# CMoy_-_OPA1622_Triple.net
KiCad netlist of a schematic drawn in EAGLE
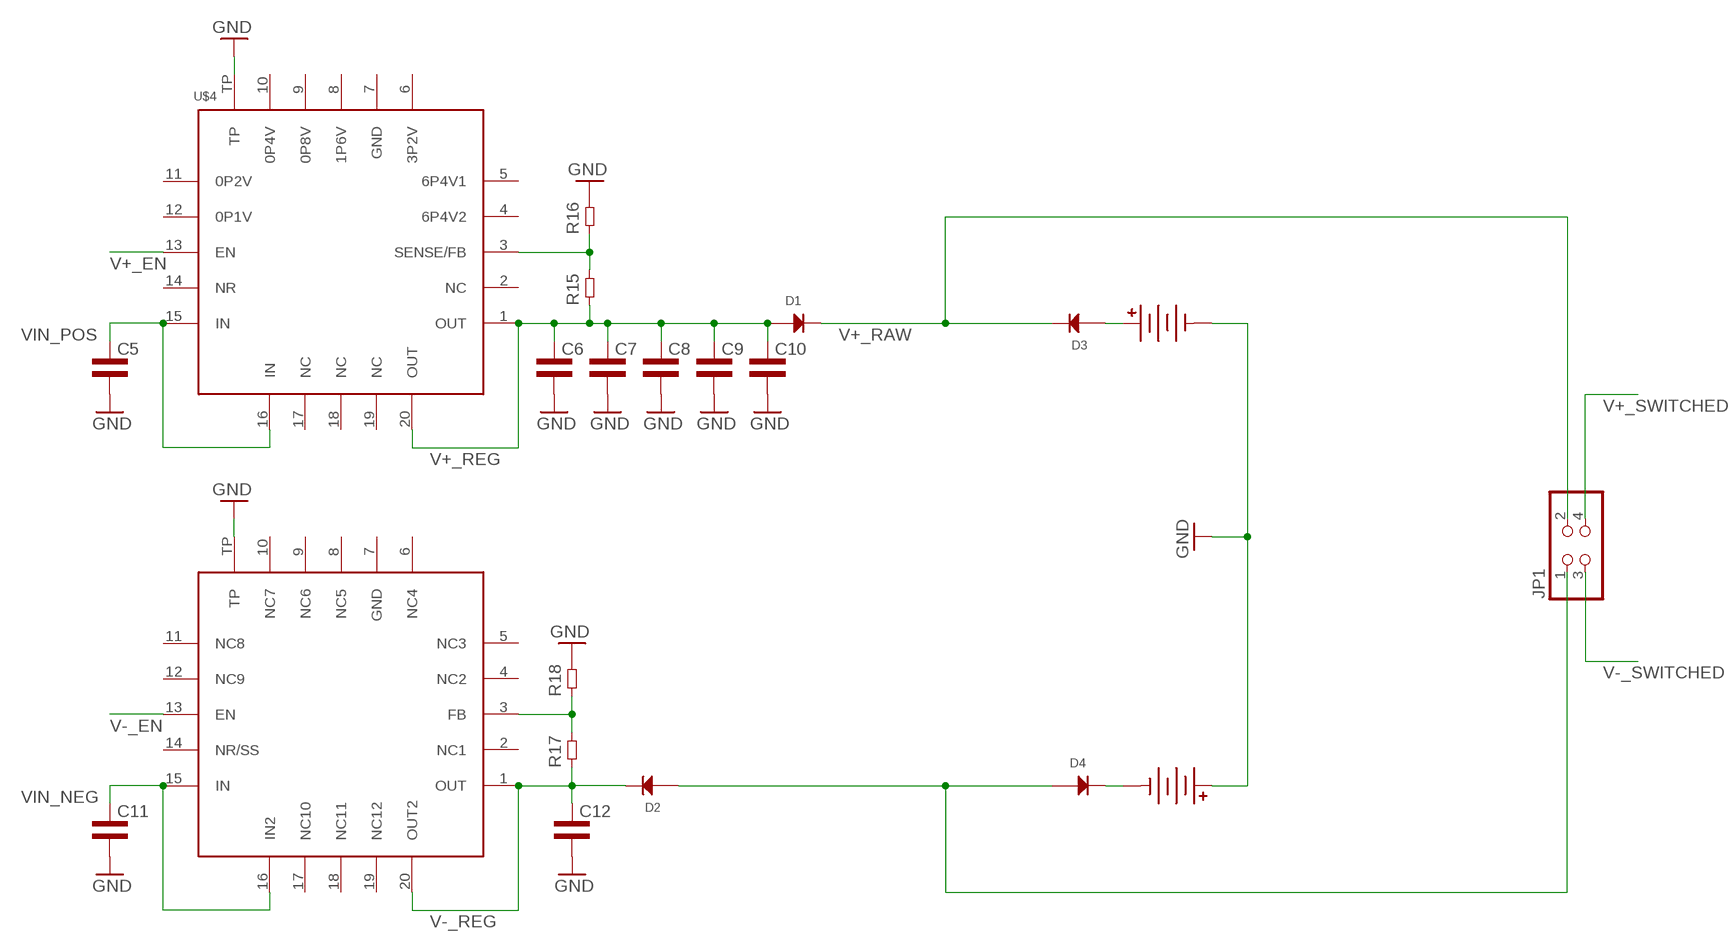
[diagram p0: schematic, sheet 1]
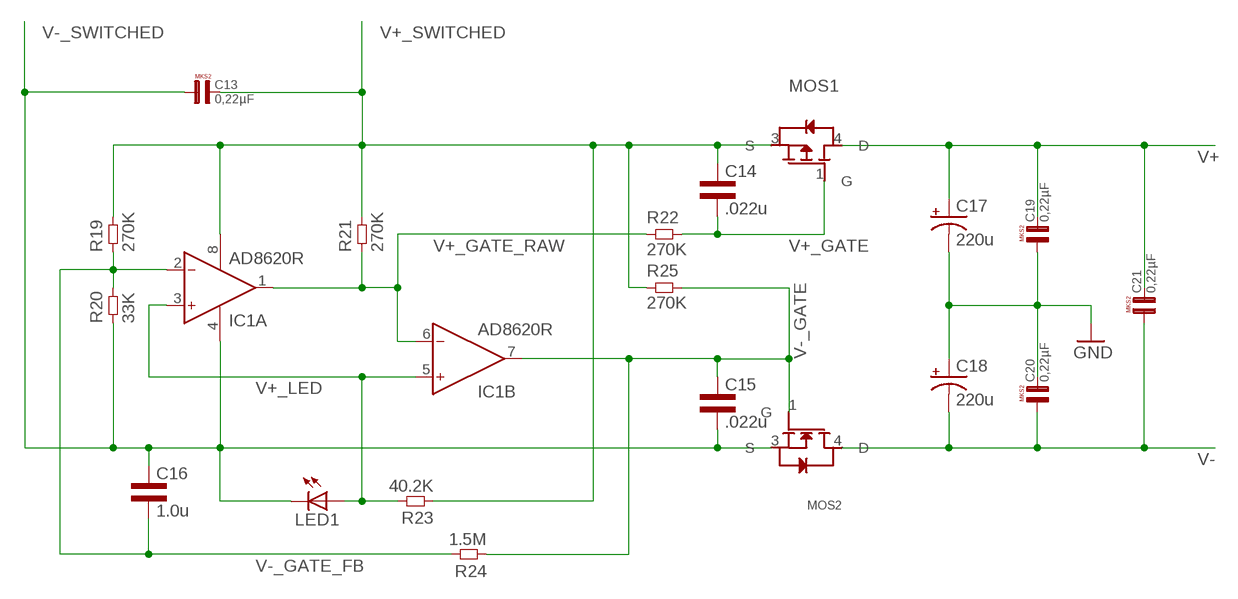
[diagram p1: schematic, sheet 2]
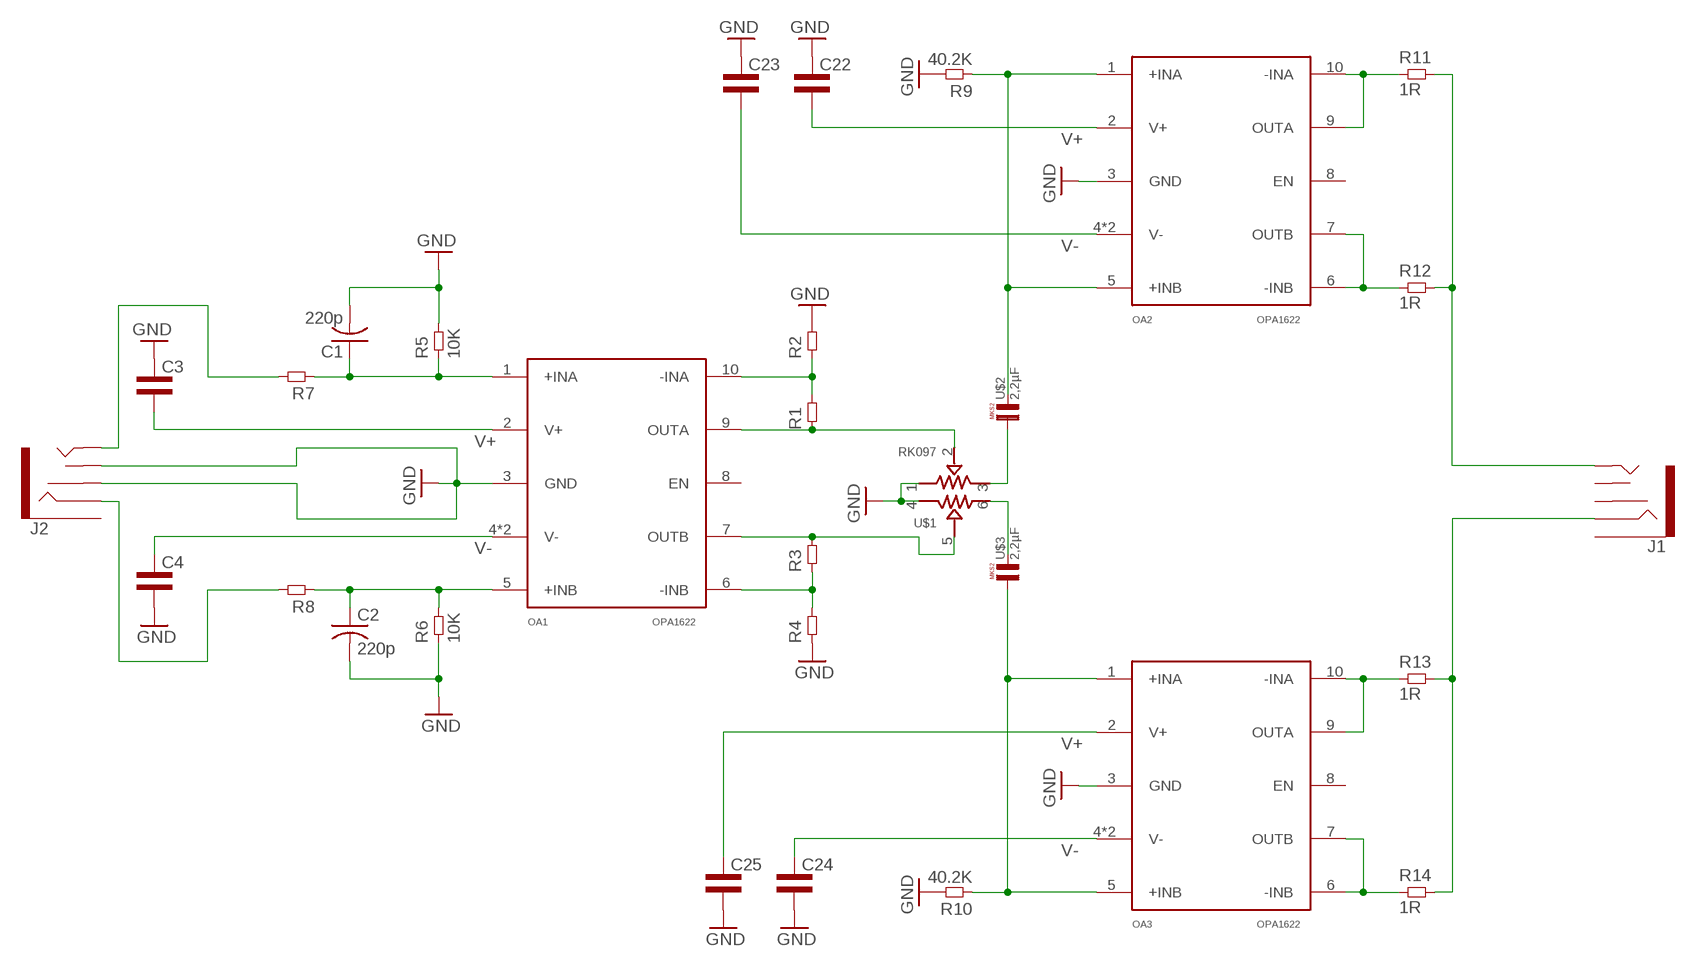
[diagram p2: schematic, sheet 3]

(export (version "E")
  (design (tool "Eeschema 10.0.6"))
  (components
    (comp (ref "C1")
      (value "220p")
      (footprint "eagle-import:C025-050X050")
      (libsource (lib "eagle-import") (part "C-US025-050X050"))
    )
    (comp (ref "C2")
      (value "220p")
      (footprint "eagle-import:C025-050X050")
      (libsource (lib "eagle-import") (part "C-US025-050X050"))
    )
    (comp (ref "C3")
      (value "CAP0603L3")
      (footprint "eagle-import:0603L3")
      (libsource (lib "eagle-import") (part "CAP0603L3"))
    )
    (comp (ref "C4")
      (value "CAP0603L3")
      (footprint "eagle-import:0603L3")
      (libsource (lib "eagle-import") (part "CAP0603L3"))
    )
    (comp (ref "C22")
      (value "CAP0603L3")
      (footprint "eagle-import:0603L3")
      (libsource (lib "eagle-import") (part "CAP0603L3"))
    )
    (comp (ref "C23")
      (value "CAP0603L3")
      (footprint "eagle-import:0603L3")
      (libsource (lib "eagle-import") (part "CAP0603L3"))
    )
    (comp (ref "C24")
      (value "CAP0603L3")
      (footprint "eagle-import:0603L3")
      (libsource (lib "eagle-import") (part "CAP0603L3"))
    )
    (comp (ref "C25")
      (value "CAP0603L3")
      (footprint "eagle-import:0603L3")
      (libsource (lib "eagle-import") (part "CAP0603L3"))
    )
    (comp (ref "J1")
      (value "AUDIO-JACK2SMD")
      (footprint "eagle-import:AUDIO-JACK-3.5MM-SMD")
      (libsource (lib "eagle-import") (part "AUDIO-JACK2SMD"))
    )
    (comp (ref "J2")
      (value "AUDIO-JACK2SMD")
      (footprint "eagle-import:AUDIO-JACK-3.5MM-SMD")
      (libsource (lib "eagle-import") (part "AUDIO-JACK2SMD"))
    )
    (comp (ref "OA1")
      (value "OPA1622")
      (footprint "eagle-import:S-PVSON-N10")
      (libsource (lib "eagle-import") (part "OPA1622"))
    )
    (comp (ref "OA2")
      (value "OPA1622")
      (footprint "eagle-import:S-PVSON-N10")
      (libsource (lib "eagle-import") (part "OPA1622"))
    )
    (comp (ref "OA3")
      (value "OPA1622")
      (footprint "eagle-import:S-PVSON-N10")
      (libsource (lib "eagle-import") (part "OPA1622"))
    )
    (comp (ref "R1")
      (value "RES0603L3")
      (footprint "eagle-import:0603L3")
      (libsource (lib "eagle-import") (part "RES0603L3"))
    )
    (comp (ref "R2")
      (value "RES0603L3")
      (footprint "eagle-import:0603L3")
      (libsource (lib "eagle-import") (part "RES0603L3"))
    )
    (comp (ref "R3")
      (value "RES0603L3")
      (footprint "eagle-import:0603L3")
      (libsource (lib "eagle-import") (part "RES0603L3"))
    )
    (comp (ref "R4")
      (value "RES0603L3")
      (footprint "eagle-import:0603L3")
      (libsource (lib "eagle-import") (part "RES0603L3"))
    )
    (comp (ref "R5")
      (value "10K")
      (footprint "eagle-import:0603L3")
      (libsource (lib "eagle-import") (part "RES0603L3"))
    )
    (comp (ref "R6")
      (value "10K")
      (footprint "eagle-import:0603L3")
      (libsource (lib "eagle-import") (part "RES0603L3"))
    )
    (comp (ref "R7")
      (value "RES0603L3")
      (footprint "eagle-import:0603L3")
      (libsource (lib "eagle-import") (part "RES0603L3"))
    )
    (comp (ref "R8")
      (value "RES0603L3")
      (footprint "eagle-import:0603L3")
      (libsource (lib "eagle-import") (part "RES0603L3"))
    )
    (comp (ref "R9")
      (value "40.2K")
      (footprint "eagle-import:0603L3")
      (libsource (lib "eagle-import") (part "RES0603L3"))
    )
    (comp (ref "R10")
      (value "40.2K")
      (footprint "eagle-import:0603L3")
      (libsource (lib "eagle-import") (part "RES0603L3"))
    )
    (comp (ref "R11")
      (value "1R")
      (footprint "eagle-import:0805L3")
      (libsource (lib "eagle-import") (part "RES0805L3"))
    )
    (comp (ref "R12")
      (value "1R")
      (footprint "eagle-import:0805L3")
      (libsource (lib "eagle-import") (part "RES0805L3"))
    )
    (comp (ref "R13")
      (value "1R")
      (footprint "eagle-import:0805L3")
      (libsource (lib "eagle-import") (part "RES0805L3"))
    )
    (comp (ref "R14")
      (value "1R")
      (footprint "eagle-import:0805L3")
      (libsource (lib "eagle-import") (part "RES0805L3"))
    )
    (comp (ref "U$1")
      (value "RK097")
      (footprint "eagle-import:RK097")
      (libsource (lib "eagle-import") (part "RK097"))
    )
    (comp (ref "U$2")
      (value "2,2µF")
      (footprint "eagle-import:R5B7K2")
      (libsource (lib "eagle-import") (part "2,2µF"))
    )
    (comp (ref "U$3")
      (value "2,2µF")
      (footprint "eagle-import:R5B7K2")
      (libsource (lib "eagle-import") (part "2,2µF"))
    )
    (comp (ref "BATT1")
      (value "BATT_9V")
      (footprint "eagle-import:9V_FEMALE")
      (libsource (lib "eagle-import") (part "BATT_9V"))
    )
    (comp (ref "BATT2")
      (value "BATT_9V")
      (footprint "eagle-import:9V_FEMALE")
      (libsource (lib "eagle-import") (part "BATT_9V"))
    )
    (comp (ref "C5")
      (value "CAP0805L3")
      (footprint "eagle-import:0805L3")
      (libsource (lib "eagle-import") (part "CAP0805L3"))
    )
    (comp (ref "C6")
      (value "CAP0805L3")
      (footprint "eagle-import:0805L3")
      (libsource (lib "eagle-import") (part "CAP0805L3"))
    )
    (comp (ref "C7")
      (value "CAP0805L3")
      (footprint "eagle-import:0805L3")
      (libsource (lib "eagle-import") (part "CAP0805L3"))
    )
    (comp (ref "C8")
      (value "CAP0805L3")
      (footprint "eagle-import:0805L3")
      (libsource (lib "eagle-import") (part "CAP0805L3"))
    )
    (comp (ref "C9")
      (value "CAP0805L3")
      (footprint "eagle-import:0805L3")
      (libsource (lib "eagle-import") (part "CAP0805L3"))
    )
    (comp (ref "C10")
      (value "CAP0805L3")
      (footprint "eagle-import:0805L3")
      (libsource (lib "eagle-import") (part "CAP0805L3"))
    )
    (comp (ref "C11")
      (value "CAP0805L3")
      (footprint "eagle-import:0805L3")
      (libsource (lib "eagle-import") (part "CAP0805L3"))
    )
    (comp (ref "C12")
      (value "CAP0805L3")
      (footprint "eagle-import:0805L3")
      (libsource (lib "eagle-import") (part "CAP0805L3"))
    )
    (comp (ref "D1")
      (value "DIODEMINI2-F3-B")
      (footprint "eagle-import:MINI2-F3-B")
      (libsource (lib "eagle-import") (part "DIODEMINI2-F3-B"))
    )
    (comp (ref "D2")
      (value "DIODEMINI2-F3-B")
      (footprint "eagle-import:MINI2-F3-B")
      (libsource (lib "eagle-import") (part "DIODEMINI2-F3-B"))
    )
    (comp (ref "D3")
      (value "DIODEMINI2-F3-B")
      (footprint "eagle-import:MINI2-F3-B")
      (libsource (lib "eagle-import") (part "DIODEMINI2-F3-B"))
    )
    (comp (ref "D4")
      (value "DIODEMINI2-F3-B")
      (footprint "eagle-import:MINI2-F3-B")
      (libsource (lib "eagle-import") (part "DIODEMINI2-F3-B"))
    )
    (comp (ref "JP1")
      (value "PINHD-2X2")
      (footprint "eagle-import:2X02")
      (libsource (lib "eagle-import") (part "PINHD-2X2"))
    )
    (comp (ref "R15")
      (value "RES0603L3")
      (footprint "eagle-import:0603L3")
      (libsource (lib "eagle-import") (part "RES0603L3"))
    )
    (comp (ref "R16")
      (value "RES0603L3")
      (footprint "eagle-import:0603L3")
      (libsource (lib "eagle-import") (part "RES0603L3"))
    )
    (comp (ref "R17")
      (value "RES0603L3")
      (footprint "eagle-import:0603L3")
      (libsource (lib "eagle-import") (part "RES0603L3"))
    )
    (comp (ref "R18")
      (value "RES0603L3")
      (footprint "eagle-import:0603L3")
      (libsource (lib "eagle-import") (part "RES0603L3"))
    )
    (comp (ref "U$4")
      (value "POWER-SUPPLY_POS_V1_TI_LDO_TPS7A4700")
      (footprint "eagle-import:POWER-SUPPLY_POS_V1_TI_LDO_VQFN-20")
      (libsource (lib "eagle-import") (part "POWER-SUPPLY_POS_V1_TI_LDO_TPS7A4700"))
    )
    (comp (ref "U$5")
      (value "POWER-SUPPLY_POS_V1_TI_LDO_TPS7A3301RGWT")
      (footprint "eagle-import:POWER-SUPPLY_POS_V1_TI_LDO_VQFN-20")
      (libsource (lib "eagle-import") (part "POWER-SUPPLY_POS_V1_TI_LDO_TPS7A3301RGWT"))
    )
    (comp (ref "C13")
      (value "0,22µF")
      (footprint "eagle-import:R5B3")
      (libsource (lib "eagle-import") (part "0,22µF"))
    )
    (comp (ref "C14")
      (value ".022u")
      (footprint "eagle-import:0603L3")
      (libsource (lib "eagle-import") (part "CAP0603L3"))
    )
    (comp (ref "C15")
      (value ".022u")
      (footprint "eagle-import:0603L3")
      (libsource (lib "eagle-import") (part "CAP0603L3"))
    )
    (comp (ref "C16")
      (value "1.0u")
      (footprint "eagle-import:0603L3")
      (libsource (lib "eagle-import") (part "CAP0603L3"))
    )
    (comp (ref "C17")
      (value "220u")
      (footprint "eagle-import:E3,5-8")
      (libsource (lib "eagle-import") (part "CPOL-USE3.5-8"))
    )
    (comp (ref "C18")
      (value "220u")
      (footprint "eagle-import:E3,5-8")
      (libsource (lib "eagle-import") (part "CPOL-USE3.5-8"))
    )
    (comp (ref "C19")
      (value "0,22µF")
      (footprint "eagle-import:R5B3")
      (libsource (lib "eagle-import") (part "0,22µF"))
    )
    (comp (ref "C20")
      (value "0,22µF")
      (footprint "eagle-import:R5B3")
      (libsource (lib "eagle-import") (part "0,22µF"))
    )
    (comp (ref "C21")
      (value "0,22µF")
      (footprint "eagle-import:R5B3")
      (libsource (lib "eagle-import") (part "0,22µF"))
    )
    (comp (ref "IC1")
      (value "AD8620R")
      (footprint "eagle-import:SO8")
      (fields (field (name "MF") "ALTERA CORPORATION") (field (name "MPN") "AD8620ARZ"))
      (libsource (lib "eagle-import") (part "AD8620R"))
    )
    (comp (ref "LED1")
      (value "LED3MM")
      (footprint "eagle-import:LED3MM")
      (libsource (lib "eagle-import") (part "LED3MM"))
    )
    (comp (ref "MOS1")
      (value "MOSFET-P")
      (footprint "eagle-import:DPAK-3")
      (libsource (lib "eagle-import") (part "MOSFET-P"))
    )
    (comp (ref "MOS2")
      (value "MOSFET-N")
      (footprint "eagle-import:DPAK-3")
      (libsource (lib "eagle-import") (part "MOSFET-N"))
    )
    (comp (ref "R19")
      (value "270K")
      (footprint "eagle-import:0603L3")
      (libsource (lib "eagle-import") (part "RES0603L3"))
    )
    (comp (ref "R20")
      (value "33K")
      (footprint "eagle-import:0603L3")
      (libsource (lib "eagle-import") (part "RES0603L3"))
    )
    (comp (ref "R21")
      (value "270K")
      (footprint "eagle-import:0603L3")
      (libsource (lib "eagle-import") (part "RES0603L3"))
    )
    (comp (ref "R22")
      (value "270K")
      (footprint "eagle-import:0603L3")
      (libsource (lib "eagle-import") (part "RES0603L3"))
    )
    (comp (ref "R23")
      (value "40.2K")
      (footprint "eagle-import:0603L3")
      (libsource (lib "eagle-import") (part "RES0603L3"))
    )
    (comp (ref "R24")
      (value "1.5M")
      (footprint "eagle-import:0603L3")
      (libsource (lib "eagle-import") (part "RES0603L3"))
    )
    (comp (ref "R25")
      (value "270K")
      (footprint "eagle-import:0603L3")
      (libsource (lib "eagle-import") (part "RES0603L3"))
    )
  )
  (nets
    (net (code "1") (name "GND") (class "Default")
      (node (ref "BATT1") (pin "N1") (pinfunction "NEG_N1") (pintype "bidirectional"))
      (node (ref "BATT1") (pin "N2") (pinfunction "NEG_N2") (pintype "bidirectional"))
      (node (ref "BATT1") (pin "N3") (pinfunction "NEG_N3") (pintype "bidirectional"))
      (node (ref "BATT2") (pin "P1") (pinfunction "POS_P1") (pintype "bidirectional"))
      (node (ref "BATT2") (pin "P2") (pinfunction "POS_P2") (pintype "bidirectional"))
      (node (ref "BATT2") (pin "P3") (pinfunction "POS_P3") (pintype "bidirectional"))
      (node (ref "C1") (pin "2") (pinfunction "2_2") (pintype "passive"))
      (node (ref "C10") (pin "2") (pinfunction "2_2") (pintype "bidirectional"))
      (node (ref "C11") (pin "2") (pinfunction "2_2") (pintype "bidirectional"))
      (node (ref "C12") (pin "2") (pinfunction "2_2") (pintype "bidirectional"))
      (node (ref "C17") (pin "-") (pinfunction "-_-") (pintype "passive"))
      (node (ref "C18") (pin "+") (pinfunction "+_+") (pintype "passive"))
      (node (ref "C19") (pin "1") (pinfunction "1_1") (pintype "passive"))
      (node (ref "C2") (pin "2") (pinfunction "2_2") (pintype "passive"))
      (node (ref "C20") (pin "2") (pinfunction "2_2") (pintype "passive"))
      (node (ref "C22") (pin "P$1") (pinfunction "1_P$1") (pintype "bidirectional"))
      (node (ref "C23") (pin "P$1") (pinfunction "1_P$1") (pintype "bidirectional"))
      (node (ref "C24") (pin "P$2") (pinfunction "2_P$2") (pintype "bidirectional"))
      (node (ref "C25") (pin "P$2") (pinfunction "2_P$2") (pintype "bidirectional"))
      (node (ref "C3") (pin "P$1") (pinfunction "1_P$1") (pintype "bidirectional"))
      (node (ref "C4") (pin "P$2") (pinfunction "2_P$2") (pintype "bidirectional"))
      (node (ref "C5") (pin "2") (pinfunction "2_2") (pintype "bidirectional"))
      (node (ref "C6") (pin "2") (pinfunction "2_2") (pintype "bidirectional"))
      (node (ref "C7") (pin "2") (pinfunction "2_2") (pintype "bidirectional"))
      (node (ref "C8") (pin "2") (pinfunction "2_2") (pintype "bidirectional"))
      (node (ref "C9") (pin "2") (pinfunction "2_2") (pintype "bidirectional"))
      (node (ref "J2") (pin "RSH") (pinfunction "RSH_RSH") (pintype "bidirectional"))
      (node (ref "J2") (pin "TSH") (pinfunction "TSH_TSH") (pintype "bidirectional"))
      (node (ref "OA1") (pin "3") (pinfunction "GND_3") (pintype "bidirectional"))
      (node (ref "OA2") (pin "3") (pinfunction "GND_3") (pintype "bidirectional"))
      (node (ref "OA3") (pin "3") (pinfunction "GND_3") (pintype "bidirectional"))
      (node (ref "R10") (pin "P$2") (pinfunction "2_P$2") (pintype "bidirectional"))
      (node (ref "R16") (pin "P$2") (pinfunction "2_P$2") (pintype "bidirectional"))
      (node (ref "R18") (pin "P$2") (pinfunction "2_P$2") (pintype "bidirectional"))
      (node (ref "R2") (pin "P$2") (pinfunction "2_P$2") (pintype "bidirectional"))
      (node (ref "R4") (pin "P$1") (pinfunction "1_P$1") (pintype "bidirectional"))
      (node (ref "R5") (pin "P$2") (pinfunction "2_P$2") (pintype "bidirectional"))
      (node (ref "R6") (pin "P$1") (pinfunction "1_P$1") (pintype "bidirectional"))
      (node (ref "R9") (pin "P$2") (pinfunction "2_P$2") (pintype "bidirectional"))
      (node (ref "U$1") (pin "1") (pinfunction "1_1") (pintype "bidirectional"))
      (node (ref "U$1") (pin "4") (pinfunction "4_4") (pintype "bidirectional"))
      (node (ref "U$4") (pin "TP") (pinfunction "TP_TP") (pintype "bidirectional"))
      (node (ref "U$5") (pin "TP") (pinfunction "TP_TP") (pintype "bidirectional"))
    )
    (net (code "2") (name "Net-(D2-ANODE)") (class "Default")
      (node (ref "D2") (pin "2") (pinfunction "ANODE_2") (pintype "bidirectional"))
      (node (ref "D4") (pin "2") (pinfunction "ANODE_2") (pintype "bidirectional"))
      (node (ref "JP1") (pin "1") (pinfunction "1_1") (pintype "passive"))
    )
    (net (code "3") (name "Net-(D3-ANODE)") (class "Default")
      (node (ref "BATT1") (pin "P1") (pinfunction "POS_P1") (pintype "bidirectional"))
      (node (ref "BATT1") (pin "P2") (pinfunction "POS_P2") (pintype "bidirectional"))
      (node (ref "BATT1") (pin "P3") (pinfunction "POS_P3") (pintype "bidirectional"))
      (node (ref "D3") (pin "2") (pinfunction "ANODE_2") (pintype "bidirectional"))
    )
    (net (code "4") (name "Net-(D4-CATHODE)") (class "Default")
      (node (ref "BATT2") (pin "N1") (pinfunction "NEG_N1") (pintype "bidirectional"))
      (node (ref "BATT2") (pin "N2") (pinfunction "NEG_N2") (pintype "bidirectional"))
      (node (ref "BATT2") (pin "N3") (pinfunction "NEG_N3") (pintype "bidirectional"))
      (node (ref "D4") (pin "1") (pinfunction "CATHODE_1") (pintype "bidirectional"))
    )
    (net (code "5") (name "Net-(J1-PadRING)") (class "Default")
      (node (ref "J1") (pin "RING") (pinfunction "RING_RING") (pintype "bidirectional"))
      (node (ref "R13") (pin "2") (pinfunction "2_2") (pintype "bidirectional"))
      (node (ref "R14") (pin "2") (pinfunction "2_2") (pintype "bidirectional"))
    )
    (net (code "6") (name "Net-(J1-PadTIP)") (class "Default")
      (node (ref "J1") (pin "TIP") (pinfunction "TIP_TIP") (pintype "bidirectional"))
      (node (ref "R11") (pin "2") (pinfunction "2_2") (pintype "bidirectional"))
      (node (ref "R12") (pin "2") (pinfunction "2_2") (pintype "bidirectional"))
    )
    (net (code "7") (name "Net-(OA1-+INA)") (class "Default")
      (node (ref "C1") (pin "1") (pinfunction "1_1") (pintype "passive"))
      (node (ref "OA1") (pin "1") (pinfunction "+INA_1") (pintype "bidirectional"))
      (node (ref "R5") (pin "P$1") (pinfunction "1_P$1") (pintype "bidirectional"))
      (node (ref "R7") (pin "P$1") (pinfunction "1_P$1") (pintype "bidirectional"))
    )
    (net (code "8") (name "Net-(OA1-+INB)") (class "Default")
      (node (ref "C2") (pin "1") (pinfunction "1_1") (pintype "passive"))
      (node (ref "OA1") (pin "5") (pinfunction "+INB_5") (pintype "bidirectional"))
      (node (ref "R6") (pin "P$2") (pinfunction "2_P$2") (pintype "bidirectional"))
      (node (ref "R8") (pin "P$1") (pinfunction "1_P$1") (pintype "bidirectional"))
    )
    (net (code "9") (name "Net-(OA1--INA)") (class "Default")
      (node (ref "OA1") (pin "10") (pinfunction "-INA_10") (pintype "bidirectional"))
      (node (ref "R1") (pin "P$2") (pinfunction "2_P$2") (pintype "bidirectional"))
      (node (ref "R2") (pin "P$1") (pinfunction "1_P$1") (pintype "bidirectional"))
    )
    (net (code "10") (name "Net-(OA1--INB)") (class "Default")
      (node (ref "OA1") (pin "6") (pinfunction "-INB_6") (pintype "bidirectional"))
      (node (ref "R3") (pin "P$1") (pinfunction "1_P$1") (pintype "bidirectional"))
      (node (ref "R4") (pin "P$2") (pinfunction "2_P$2") (pintype "bidirectional"))
    )
    (net (code "11") (name "Net-(OA1-OUTA)") (class "Default")
      (node (ref "OA1") (pin "9") (pinfunction "OUTA_9") (pintype "bidirectional"))
      (node (ref "R1") (pin "P$1") (pinfunction "1_P$1") (pintype "bidirectional"))
      (node (ref "U$1") (pin "2") (pinfunction "2_2") (pintype "bidirectional"))
    )
    (net (code "12") (name "Net-(OA1-OUTB)") (class "Default")
      (node (ref "OA1") (pin "7") (pinfunction "OUTB_7") (pintype "bidirectional"))
      (node (ref "R3") (pin "P$2") (pinfunction "2_P$2") (pintype "bidirectional"))
      (node (ref "U$1") (pin "5") (pinfunction "5_5") (pintype "bidirectional"))
    )
    (net (code "13") (name "Net-(OA2-+INA)") (class "Default")
      (node (ref "OA2") (pin "1") (pinfunction "+INA_1") (pintype "bidirectional"))
      (node (ref "OA2") (pin "5") (pinfunction "+INB_5") (pintype "bidirectional"))
      (node (ref "R9") (pin "P$1") (pinfunction "1_P$1") (pintype "bidirectional"))
      (node (ref "U$2") (pin "2") (pinfunction "2_2") (pintype "passive"))
    )
    (net (code "14") (name "Net-(OA2--INA)") (class "Default")
      (node (ref "OA2") (pin "10") (pinfunction "-INA_10") (pintype "bidirectional"))
      (node (ref "OA2") (pin "9") (pinfunction "OUTA_9") (pintype "bidirectional"))
      (node (ref "R11") (pin "1") (pinfunction "1_1") (pintype "bidirectional"))
    )
    (net (code "15") (name "Net-(OA2--INB)") (class "Default")
      (node (ref "OA2") (pin "6") (pinfunction "-INB_6") (pintype "bidirectional"))
      (node (ref "OA2") (pin "7") (pinfunction "OUTB_7") (pintype "bidirectional"))
      (node (ref "R12") (pin "1") (pinfunction "1_1") (pintype "bidirectional"))
    )
    (net (code "16") (name "Net-(OA3-+INA)") (class "Default")
      (node (ref "OA3") (pin "1") (pinfunction "+INA_1") (pintype "bidirectional"))
      (node (ref "OA3") (pin "5") (pinfunction "+INB_5") (pintype "bidirectional"))
      (node (ref "R10") (pin "P$1") (pinfunction "1_P$1") (pintype "bidirectional"))
      (node (ref "U$3") (pin "1") (pinfunction "1_1") (pintype "passive"))
    )
    (net (code "17") (name "Net-(OA3--INA)") (class "Default")
      (node (ref "OA3") (pin "10") (pinfunction "-INA_10") (pintype "bidirectional"))
      (node (ref "OA3") (pin "9") (pinfunction "OUTA_9") (pintype "bidirectional"))
      (node (ref "R13") (pin "1") (pinfunction "1_1") (pintype "bidirectional"))
    )
    (net (code "18") (name "Net-(OA3--INB)") (class "Default")
      (node (ref "OA3") (pin "6") (pinfunction "-INB_6") (pintype "bidirectional"))
      (node (ref "OA3") (pin "7") (pinfunction "OUTB_7") (pintype "bidirectional"))
      (node (ref "R14") (pin "1") (pinfunction "1_1") (pintype "bidirectional"))
    )
    (net (code "19") (name "Net-(R7-2)") (class "Default")
      (node (ref "J2") (pin "TIP") (pinfunction "TIP_TIP") (pintype "bidirectional"))
      (node (ref "R7") (pin "P$2") (pinfunction "2_P$2") (pintype "bidirectional"))
    )
    (net (code "20") (name "Net-(R8-2)") (class "Default")
      (node (ref "J2") (pin "RING") (pinfunction "RING_RING") (pintype "bidirectional"))
      (node (ref "R8") (pin "P$2") (pinfunction "2_P$2") (pintype "bidirectional"))
    )
    (net (code "21") (name "Net-(R15-2)") (class "Default")
      (node (ref "R15") (pin "P$2") (pinfunction "2_P$2") (pintype "bidirectional"))
      (node (ref "R16") (pin "P$1") (pinfunction "1_P$1") (pintype "bidirectional"))
      (node (ref "U$4") (pin "3") (pinfunction "SENSE/FB_3") (pintype "bidirectional"))
    )
    (net (code "22") (name "Net-(R17-2)") (class "Default")
      (node (ref "R17") (pin "P$2") (pinfunction "2_P$2") (pintype "bidirectional"))
      (node (ref "R18") (pin "P$1") (pinfunction "1_P$1") (pintype "bidirectional"))
      (node (ref "U$5") (pin "3") (pinfunction "FB_3") (pintype "bidirectional"))
    )
    (net (code "23") (name "Net-(U$1-Pad3)") (class "Default")
      (node (ref "U$1") (pin "3") (pinfunction "3_3") (pintype "bidirectional"))
      (node (ref "U$2") (pin "1") (pinfunction "1_1") (pintype "passive"))
    )
    (net (code "24") (name "Net-(U$1-Pad6)") (class "Default")
      (node (ref "U$1") (pin "6") (pinfunction "6_6") (pintype "bidirectional"))
      (node (ref "U$3") (pin "2") (pinfunction "2_2") (pintype "passive"))
    )
    (net (code "25") (name "V+") (class "Default")
      (node (ref "C17") (pin "+") (pinfunction "+_+") (pintype "passive"))
      (node (ref "C19") (pin "2") (pinfunction "2_2") (pintype "passive"))
      (node (ref "C21") (pin "2") (pinfunction "2_2") (pintype "passive"))
      (node (ref "C22") (pin "P$2") (pinfunction "2_P$2") (pintype "bidirectional"))
      (node (ref "C25") (pin "P$1") (pinfunction "1_P$1") (pintype "bidirectional"))
      (node (ref "C3") (pin "P$2") (pinfunction "2_P$2") (pintype "bidirectional"))
      (node (ref "MOS1") (pin "4") (pinfunction "D_4") (pintype "bidirectional"))
      (node (ref "OA1") (pin "2") (pinfunction "V+_2") (pintype "bidirectional"))
      (node (ref "OA2") (pin "2") (pinfunction "V+_2") (pintype "bidirectional"))
      (node (ref "OA3") (pin "2") (pinfunction "V+_2") (pintype "bidirectional"))
    )
    (net (code "26") (name "V+_EN") (class "Default")
      (node (ref "U$4") (pin "13") (pinfunction "EN_13") (pintype "bidirectional"))
    )
    (net (code "27") (name "V+_GATE") (class "Default")
      (node (ref "C14") (pin "P$2") (pinfunction "2_P$2") (pintype "bidirectional"))
      (node (ref "MOS1") (pin "1") (pinfunction "G_1") (pintype "bidirectional"))
      (node (ref "R22") (pin "P$2") (pinfunction "2_P$2") (pintype "bidirectional"))
    )
    (net (code "28") (name "V+_GATE_RAW") (class "Default")
      (node (ref "IC1") (pin "1") (pinfunction "OUT_1") (pintype "output"))
      (node (ref "IC1") (pin "6") (pinfunction "IN-_6") (pintype "input"))
      (node (ref "R21") (pin "P$1") (pinfunction "1_P$1") (pintype "bidirectional"))
      (node (ref "R22") (pin "P$1") (pinfunction "1_P$1") (pintype "bidirectional"))
    )
    (net (code "29") (name "V+_LED") (class "Default")
      (node (ref "IC1") (pin "3") (pinfunction "IN+_3") (pintype "input"))
      (node (ref "IC1") (pin "5") (pinfunction "IN+_5") (pintype "input"))
      (node (ref "LED1") (pin "A") (pinfunction "A_A") (pintype "passive"))
      (node (ref "R23") (pin "P$2") (pinfunction "2_P$2") (pintype "bidirectional"))
    )
    (net (code "30") (name "V+_RAW") (class "Default")
      (node (ref "D1") (pin "1") (pinfunction "CATHODE_1") (pintype "bidirectional"))
      (node (ref "D3") (pin "1") (pinfunction "CATHODE_1") (pintype "bidirectional"))
      (node (ref "JP1") (pin "2") (pinfunction "2_2") (pintype "passive"))
    )
    (net (code "31") (name "V+_REG") (class "Default")
      (node (ref "C10") (pin "1") (pinfunction "1_1") (pintype "bidirectional"))
      (node (ref "C6") (pin "1") (pinfunction "1_1") (pintype "bidirectional"))
      (node (ref "C7") (pin "1") (pinfunction "1_1") (pintype "bidirectional"))
      (node (ref "C8") (pin "1") (pinfunction "1_1") (pintype "bidirectional"))
      (node (ref "C9") (pin "1") (pinfunction "1_1") (pintype "bidirectional"))
      (node (ref "D1") (pin "2") (pinfunction "ANODE_2") (pintype "bidirectional"))
      (node (ref "R15") (pin "P$1") (pinfunction "1_P$1") (pintype "bidirectional"))
      (node (ref "U$4") (pin "1") (pinfunction "OUT_1") (pintype "bidirectional"))
      (node (ref "U$4") (pin "20") (pinfunction "OUT_20") (pintype "bidirectional"))
    )
    (net (code "32") (name "V+_SWITCHED") (class "Default")
      (node (ref "C13") (pin "2") (pinfunction "2_2") (pintype "passive"))
      (node (ref "C14") (pin "P$1") (pinfunction "1_P$1") (pintype "bidirectional"))
      (node (ref "IC1") (pin "8") (pinfunction "V+_8") (pintype "power_in"))
      (node (ref "JP1") (pin "4") (pinfunction "4_4") (pintype "passive"))
      (node (ref "MOS1") (pin "3") (pinfunction "S_3") (pintype "bidirectional"))
      (node (ref "R19") (pin "P$2") (pinfunction "2_P$2") (pintype "bidirectional"))
      (node (ref "R21") (pin "P$2") (pinfunction "2_P$2") (pintype "bidirectional"))
      (node (ref "R23") (pin "P$1") (pinfunction "1_P$1") (pintype "bidirectional"))
      (node (ref "R25") (pin "P$1") (pinfunction "1_P$1") (pintype "bidirectional"))
    )
    (net (code "33") (name "V-") (class "Default")
      (node (ref "C18") (pin "-") (pinfunction "-_-") (pintype "passive"))
      (node (ref "C20") (pin "1") (pinfunction "1_1") (pintype "passive"))
      (node (ref "C21") (pin "1") (pinfunction "1_1") (pintype "passive"))
      (node (ref "C23") (pin "P$2") (pinfunction "2_P$2") (pintype "bidirectional"))
      (node (ref "C24") (pin "P$1") (pinfunction "1_P$1") (pintype "bidirectional"))
      (node (ref "C4") (pin "P$1") (pinfunction "1_P$1") (pintype "bidirectional"))
      (node (ref "MOS2") (pin "4") (pinfunction "D_4") (pintype "bidirectional"))
      (node (ref "OA1") (pin "4") (pinfunction "V-_4") (pintype "bidirectional"))
      (node (ref "OA1") (pin "TP") (pinfunction "V-_TP") (pintype "bidirectional"))
      (node (ref "OA2") (pin "4") (pinfunction "V-_4") (pintype "bidirectional"))
      (node (ref "OA2") (pin "TP") (pinfunction "V-_TP") (pintype "bidirectional"))
      (node (ref "OA3") (pin "4") (pinfunction "V-_4") (pintype "bidirectional"))
      (node (ref "OA3") (pin "TP") (pinfunction "V-_TP") (pintype "bidirectional"))
    )
    (net (code "34") (name "V-_EN") (class "Default")
      (node (ref "U$5") (pin "13") (pinfunction "EN_13") (pintype "bidirectional"))
    )
    (net (code "35") (name "V-_GATE") (class "Default")
      (node (ref "C15") (pin "P$1") (pinfunction "1_P$1") (pintype "bidirectional"))
      (node (ref "IC1") (pin "7") (pinfunction "OUT_7") (pintype "output"))
      (node (ref "MOS2") (pin "1") (pinfunction "G_1") (pintype "bidirectional"))
      (node (ref "R24") (pin "P$1") (pinfunction "1_P$1") (pintype "bidirectional"))
      (node (ref "R25") (pin "P$2") (pinfunction "2_P$2") (pintype "bidirectional"))
    )
    (net (code "36") (name "V-_GATE_FB") (class "Default")
      (node (ref "C16") (pin "P$2") (pinfunction "2_P$2") (pintype "bidirectional"))
      (node (ref "IC1") (pin "2") (pinfunction "IN-_2") (pintype "input"))
      (node (ref "R19") (pin "P$1") (pinfunction "1_P$1") (pintype "bidirectional"))
      (node (ref "R20") (pin "P$2") (pinfunction "2_P$2") (pintype "bidirectional"))
      (node (ref "R24") (pin "P$2") (pinfunction "2_P$2") (pintype "bidirectional"))
    )
    (net (code "37") (name "V-_REG") (class "Default")
      (node (ref "C12") (pin "1") (pinfunction "1_1") (pintype "bidirectional"))
      (node (ref "D2") (pin "1") (pinfunction "CATHODE_1") (pintype "bidirectional"))
      (node (ref "R17") (pin "P$1") (pinfunction "1_P$1") (pintype "bidirectional"))
      (node (ref "U$5") (pin "1") (pinfunction "OUT_1") (pintype "bidirectional"))
      (node (ref "U$5") (pin "20") (pinfunction "OUT2_20") (pintype "bidirectional"))
    )
    (net (code "38") (name "V-_SWITCHED") (class "Default")
      (node (ref "C13") (pin "1") (pinfunction "1_1") (pintype "passive"))
      (node (ref "C15") (pin "P$2") (pinfunction "2_P$2") (pintype "bidirectional"))
      (node (ref "C16") (pin "P$1") (pinfunction "1_P$1") (pintype "bidirectional"))
      (node (ref "IC1") (pin "4") (pinfunction "V-_4") (pintype "power_in"))
      (node (ref "JP1") (pin "3") (pinfunction "3_3") (pintype "passive"))
      (node (ref "LED1") (pin "K") (pinfunction "C_K") (pintype "passive"))
      (node (ref "MOS2") (pin "3") (pinfunction "S_3") (pintype "bidirectional"))
      (node (ref "R20") (pin "P$1") (pinfunction "1_P$1") (pintype "bidirectional"))
    )
    (net (code "39") (name "VIN_NEG") (class "Default")
      (node (ref "C11") (pin "1") (pinfunction "1_1") (pintype "bidirectional"))
      (node (ref "U$5") (pin "15") (pinfunction "IN_15") (pintype "bidirectional"))
      (node (ref "U$5") (pin "16") (pinfunction "IN2_16") (pintype "bidirectional"))
    )
    (net (code "40") (name "VIN_POS") (class "Default")
      (node (ref "C5") (pin "1") (pinfunction "1_1") (pintype "bidirectional"))
      (node (ref "U$4") (pin "15") (pinfunction "IN_15") (pintype "bidirectional"))
      (node (ref "U$4") (pin "16") (pinfunction "IN_16") (pintype "bidirectional"))
    )
    (net (code "41") (name "unconnected-(J1-PadRSH)") (class "Default")
      (node (ref "J1") (pin "RSH") (pinfunction "RSH_RSH") (pintype "bidirectional"))
    )
    (net (code "42") (name "unconnected-(J1-PadSLEEVE)") (class "Default")
      (node (ref "J1") (pin "SLEEVE") (pinfunction "SLEEVE_SLEEVE") (pintype "bidirectional"))
    )
    (net (code "43") (name "unconnected-(J1-PadTSH)") (class "Default")
      (node (ref "J1") (pin "TSH") (pinfunction "TSH_TSH") (pintype "bidirectional"))
    )
    (net (code "44") (name "unconnected-(J2-PadSLEEVE)") (class "Default")
      (node (ref "J2") (pin "SLEEVE") (pinfunction "SLEEVE_SLEEVE") (pintype "bidirectional"))
    )
    (net (code "45") (name "unconnected-(OA1-EN-Pad8)") (class "Default")
      (node (ref "OA1") (pin "8") (pinfunction "EN_8") (pintype "bidirectional"))
    )
    (net (code "46") (name "unconnected-(OA2-EN-Pad8)") (class "Default")
      (node (ref "OA2") (pin "8") (pinfunction "EN_8") (pintype "bidirectional"))
    )
    (net (code "47") (name "unconnected-(OA3-EN-Pad8)") (class "Default")
      (node (ref "OA3") (pin "8") (pinfunction "EN_8") (pintype "bidirectional"))
    )
    (net (code "48") (name "unconnected-(U$4-0P1V-Pad12)") (class "Default")
      (node (ref "U$4") (pin "12") (pinfunction "0P1V_12") (pintype "bidirectional"))
    )
    (net (code "49") (name "unconnected-(U$4-0P2V-Pad11)") (class "Default")
      (node (ref "U$4") (pin "11") (pinfunction "0P2V_11") (pintype "bidirectional"))
    )
    (net (code "50") (name "unconnected-(U$4-0P4V-Pad10)") (class "Default")
      (node (ref "U$4") (pin "10") (pinfunction "0P4V_10") (pintype "bidirectional"))
    )
    (net (code "51") (name "unconnected-(U$4-0P8V-Pad9)") (class "Default")
      (node (ref "U$4") (pin "9") (pinfunction "0P8V_9") (pintype "bidirectional"))
    )
    (net (code "52") (name "unconnected-(U$4-1P6V-Pad8)") (class "Default")
      (node (ref "U$4") (pin "8") (pinfunction "1P6V_8") (pintype "bidirectional"))
    )
    (net (code "53") (name "unconnected-(U$4-3P2V-Pad6)") (class "Default")
      (node (ref "U$4") (pin "6") (pinfunction "3P2V_6") (pintype "bidirectional"))
    )
    (net (code "54") (name "unconnected-(U$4-6P4V1-Pad5)") (class "Default")
      (node (ref "U$4") (pin "5") (pinfunction "6P4V1_5") (pintype "bidirectional"))
    )
    (net (code "55") (name "unconnected-(U$4-6P4V2-Pad4)") (class "Default")
      (node (ref "U$4") (pin "4") (pinfunction "6P4V2_4") (pintype "bidirectional"))
    )
    (net (code "56") (name "unconnected-(U$4-GND-Pad7)") (class "Default")
      (node (ref "U$4") (pin "7") (pinfunction "GND_7") (pintype "bidirectional"))
    )
    (net (code "57") (name "unconnected-(U$4-NC-Pad2)") (class "Default")
      (node (ref "U$4") (pin "2") (pinfunction "NC_2") (pintype "bidirectional"))
    )
    (net (code "58") (name "unconnected-(U$4-NC-Pad17)") (class "Default")
      (node (ref "U$4") (pin "17") (pinfunction "NC_17") (pintype "bidirectional"))
    )
    (net (code "59") (name "unconnected-(U$4-NC-Pad18)") (class "Default")
      (node (ref "U$4") (pin "18") (pinfunction "NC_18") (pintype "bidirectional"))
    )
    (net (code "60") (name "unconnected-(U$4-NC-Pad19)") (class "Default")
      (node (ref "U$4") (pin "19") (pinfunction "NC_19") (pintype "bidirectional"))
    )
    (net (code "61") (name "unconnected-(U$4-NR-Pad14)") (class "Default")
      (node (ref "U$4") (pin "14") (pinfunction "NR_14") (pintype "bidirectional"))
    )
    (net (code "62") (name "unconnected-(U$5-GND-Pad7)") (class "Default")
      (node (ref "U$5") (pin "7") (pinfunction "GND_7") (pintype "bidirectional"))
    )
    (net (code "63") (name "unconnected-(U$5-NC1-Pad2)") (class "Default")
      (node (ref "U$5") (pin "2") (pinfunction "NC1_2") (pintype "bidirectional"))
    )
    (net (code "64") (name "unconnected-(U$5-NC2-Pad4)") (class "Default")
      (node (ref "U$5") (pin "4") (pinfunction "NC2_4") (pintype "bidirectional"))
    )
    (net (code "65") (name "unconnected-(U$5-NC3-Pad5)") (class "Default")
      (node (ref "U$5") (pin "5") (pinfunction "NC3_5") (pintype "bidirectional"))
    )
    (net (code "66") (name "unconnected-(U$5-NC4-Pad6)") (class "Default")
      (node (ref "U$5") (pin "6") (pinfunction "NC4_6") (pintype "bidirectional"))
    )
    (net (code "67") (name "unconnected-(U$5-NC5-Pad8)") (class "Default")
      (node (ref "U$5") (pin "8") (pinfunction "NC5_8") (pintype "bidirectional"))
    )
    (net (code "68") (name "unconnected-(U$5-NC6-Pad9)") (class "Default")
      (node (ref "U$5") (pin "9") (pinfunction "NC6_9") (pintype "bidirectional"))
    )
    (net (code "69") (name "unconnected-(U$5-NC7-Pad10)") (class "Default")
      (node (ref "U$5") (pin "10") (pinfunction "NC7_10") (pintype "bidirectional"))
    )
    (net (code "70") (name "unconnected-(U$5-NC8-Pad11)") (class "Default")
      (node (ref "U$5") (pin "11") (pinfunction "NC8_11") (pintype "bidirectional"))
    )
    (net (code "71") (name "unconnected-(U$5-NC9-Pad12)") (class "Default")
      (node (ref "U$5") (pin "12") (pinfunction "NC9_12") (pintype "bidirectional"))
    )
    (net (code "72") (name "unconnected-(U$5-NC10-Pad17)") (class "Default")
      (node (ref "U$5") (pin "17") (pinfunction "NC10_17") (pintype "bidirectional"))
    )
    (net (code "73") (name "unconnected-(U$5-NC11-Pad18)") (class "Default")
      (node (ref "U$5") (pin "18") (pinfunction "NC11_18") (pintype "bidirectional"))
    )
    (net (code "74") (name "unconnected-(U$5-NC12-Pad19)") (class "Default")
      (node (ref "U$5") (pin "19") (pinfunction "NC12_19") (pintype "bidirectional"))
    )
    (net (code "75") (name "unconnected-(U$5-NR{slash}SS-Pad14)") (class "Default")
      (node (ref "U$5") (pin "14") (pinfunction "NR/SS_14") (pintype "bidirectional"))
    )
  )
)
